# LED.net
KiCad netlist of a schematic drawn in Altium Designer
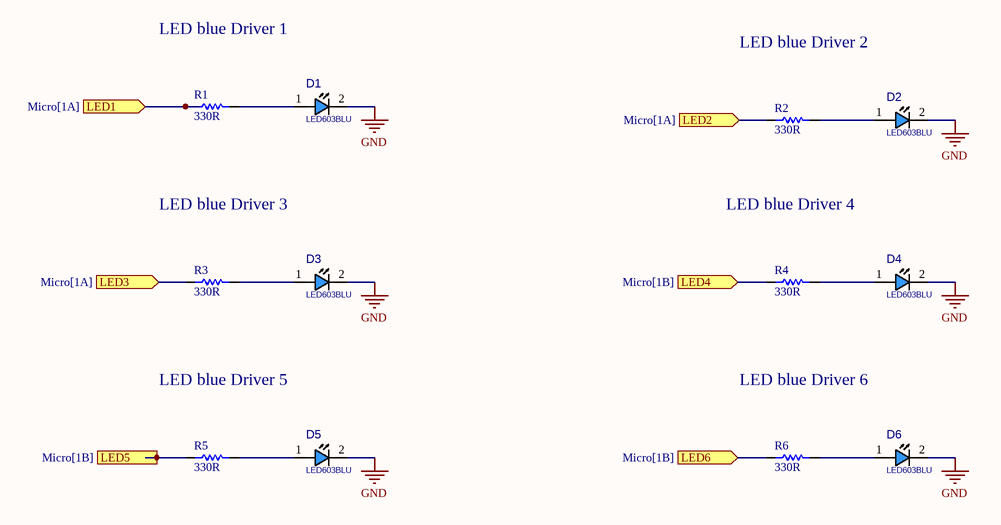
[diagram p0: LED.SchDoc]

(export (version "E")
  (design (tool "Eeschema 10.0.6"))
  (components
    (comp (ref "D1")
      (value "LED603BLU")
      (footprint "LED0603BLU")
      (description "LED, SMD, 0603, BLUE")
      (fields (field (name "MANF") "MANF") (field (name "MANF_P#") "MANF_PART#"))
      (libsource (lib "led(diode)") (part "LED_SMD_0603_BLU"))
    )
    (comp (ref "D2")
      (value "LED603BLU")
      (footprint "LED0603BLU")
      (description "LED, SMD, 0603, BLUE")
      (fields (field (name "MANF") "MANF") (field (name "MANF_P#") "MANF_PART#"))
      (libsource (lib "led(diode)") (part "LED_SMD_0603_BLU"))
    )
    (comp (ref "D3")
      (value "LED603BLU")
      (footprint "LED0603BLU")
      (description "LED, SMD, 0603, BLUE")
      (fields (field (name "MANF") "MANF") (field (name "MANF_P#") "MANF_PART#"))
      (libsource (lib "led(diode)") (part "LED_SMD_0603_BLU"))
    )
    (comp (ref "D4")
      (value "LED603BLU")
      (footprint "LED0603BLU")
      (description "LED, SMD, 0603, BLUE")
      (fields (field (name "MANF") "MANF") (field (name "MANF_P#") "MANF_PART#"))
      (libsource (lib "led(diode)") (part "LED_SMD_0603_BLU"))
    )
    (comp (ref "D5")
      (value "LED603BLU")
      (footprint "LED0603BLU")
      (description "LED, SMD, 0603, BLUE")
      (fields (field (name "MANF") "MANF") (field (name "MANF_P#") "MANF_PART#"))
      (libsource (lib "led(diode)") (part "LED_SMD_0603_BLU"))
    )
    (comp (ref "D6")
      (value "LED603BLU")
      (footprint "LED0603BLU")
      (description "LED, SMD, 0603, BLUE")
      (fields (field (name "MANF") "MANF") (field (name "MANF_P#") "MANF_PART#"))
      (libsource (lib "led(diode)") (part "LED_SMD_0603_BLU"))
    )
    (comp (ref "R1")
      (value "330R")
      (footprint "RES 0805-MIL")
      (description "Resistor")
      (fields (field (name "TOLERANCE") "5%") (field (name "POWER") "1/8 W"))
      (libsource (lib "PCBnets Library") (part "Resistor SMD"))
    )
    (comp (ref "R2")
      (value "330R")
      (footprint "RES 0805-MIL")
      (description "Resistor")
      (fields (field (name "TOLERANCE") "5%") (field (name "POWER") "1/8 W"))
      (libsource (lib "PCBnets Library") (part "Resistor SMD"))
    )
    (comp (ref "R3")
      (value "330R")
      (footprint "RES 0805-MIL")
      (description "Resistor")
      (fields (field (name "TOLERANCE") "5%") (field (name "POWER") "1/8 W"))
      (libsource (lib "PCBnets Library") (part "Resistor SMD"))
    )
    (comp (ref "R4")
      (value "330R")
      (footprint "RES 0805-MIL")
      (description "Resistor")
      (fields (field (name "TOLERANCE") "5%") (field (name "POWER") "1/8 W"))
      (libsource (lib "PCBnets Library") (part "Resistor SMD"))
    )
    (comp (ref "R5")
      (value "330R")
      (footprint "RES 0805-MIL")
      (description "Resistor")
      (fields (field (name "TOLERANCE") "5%") (field (name "POWER") "1/8 W"))
      (libsource (lib "PCBnets Library") (part "Resistor SMD"))
    )
    (comp (ref "R6")
      (value "330R")
      (footprint "RES 0805-MIL")
      (description "Resistor")
      (fields (field (name "TOLERANCE") "5%") (field (name "POWER") "1/8 W"))
      (libsource (lib "PCBnets Library") (part "Resistor SMD"))
    )
  )
  (nets
    (net (code "1") (name "/LED1") (class "Default")
      (node (ref "R1") (pin "1") (pinfunction "1_1") (pintype "passive"))
    )
    (net (code "2") (name "/LED2") (class "Default")
      (node (ref "R2") (pin "1") (pinfunction "1_1") (pintype "passive"))
    )
    (net (code "3") (name "/LED3") (class "Default")
      (node (ref "R3") (pin "1") (pinfunction "1_1") (pintype "passive"))
    )
    (net (code "4") (name "/LED4") (class "Default")
      (node (ref "R4") (pin "1") (pinfunction "1_1") (pintype "passive"))
    )
    (net (code "5") (name "/LED5") (class "Default")
      (node (ref "R5") (pin "1") (pinfunction "1_1") (pintype "passive"))
    )
    (net (code "6") (name "/LED6") (class "Default")
      (node (ref "R6") (pin "1") (pinfunction "1_1") (pintype "passive"))
    )
    (net (code "7") (name "GND") (class "Default")
      (node (ref "D1") (pin "2") (pinfunction "CATHODE_2") (pintype "passive"))
      (node (ref "D2") (pin "2") (pinfunction "CATHODE_2") (pintype "passive"))
      (node (ref "D3") (pin "2") (pinfunction "CATHODE_2") (pintype "passive"))
      (node (ref "D4") (pin "2") (pinfunction "CATHODE_2") (pintype "passive"))
      (node (ref "D5") (pin "2") (pinfunction "CATHODE_2") (pintype "passive"))
      (node (ref "D6") (pin "2") (pinfunction "CATHODE_2") (pintype "passive"))
    )
    (net (code "8") (name "Net-(D1-ANODE)") (class "Default")
      (node (ref "D1") (pin "1") (pinfunction "ANODE_1") (pintype "passive"))
      (node (ref "R1") (pin "2") (pinfunction "2_2") (pintype "passive"))
    )
    (net (code "9") (name "Net-(D2-ANODE)") (class "Default")
      (node (ref "D2") (pin "1") (pinfunction "ANODE_1") (pintype "passive"))
      (node (ref "R2") (pin "2") (pinfunction "2_2") (pintype "passive"))
    )
    (net (code "10") (name "Net-(D3-ANODE)") (class "Default")
      (node (ref "D3") (pin "1") (pinfunction "ANODE_1") (pintype "passive"))
      (node (ref "R3") (pin "2") (pinfunction "2_2") (pintype "passive"))
    )
    (net (code "11") (name "Net-(D4-ANODE)") (class "Default")
      (node (ref "D4") (pin "1") (pinfunction "ANODE_1") (pintype "passive"))
      (node (ref "R4") (pin "2") (pinfunction "2_2") (pintype "passive"))
    )
    (net (code "12") (name "Net-(D5-ANODE)") (class "Default")
      (node (ref "D5") (pin "1") (pinfunction "ANODE_1") (pintype "passive"))
      (node (ref "R5") (pin "2") (pinfunction "2_2") (pintype "passive"))
    )
    (net (code "13") (name "Net-(D6-ANODE)") (class "Default")
      (node (ref "D6") (pin "1") (pinfunction "ANODE_1") (pintype "passive"))
      (node (ref "R6") (pin "2") (pinfunction "2_2") (pintype "passive"))
    )
  )
)
